# 1-Schematic_8052Explorer_JOLLY.net
KiCad netlist of a schematic drawn in EasyEDA
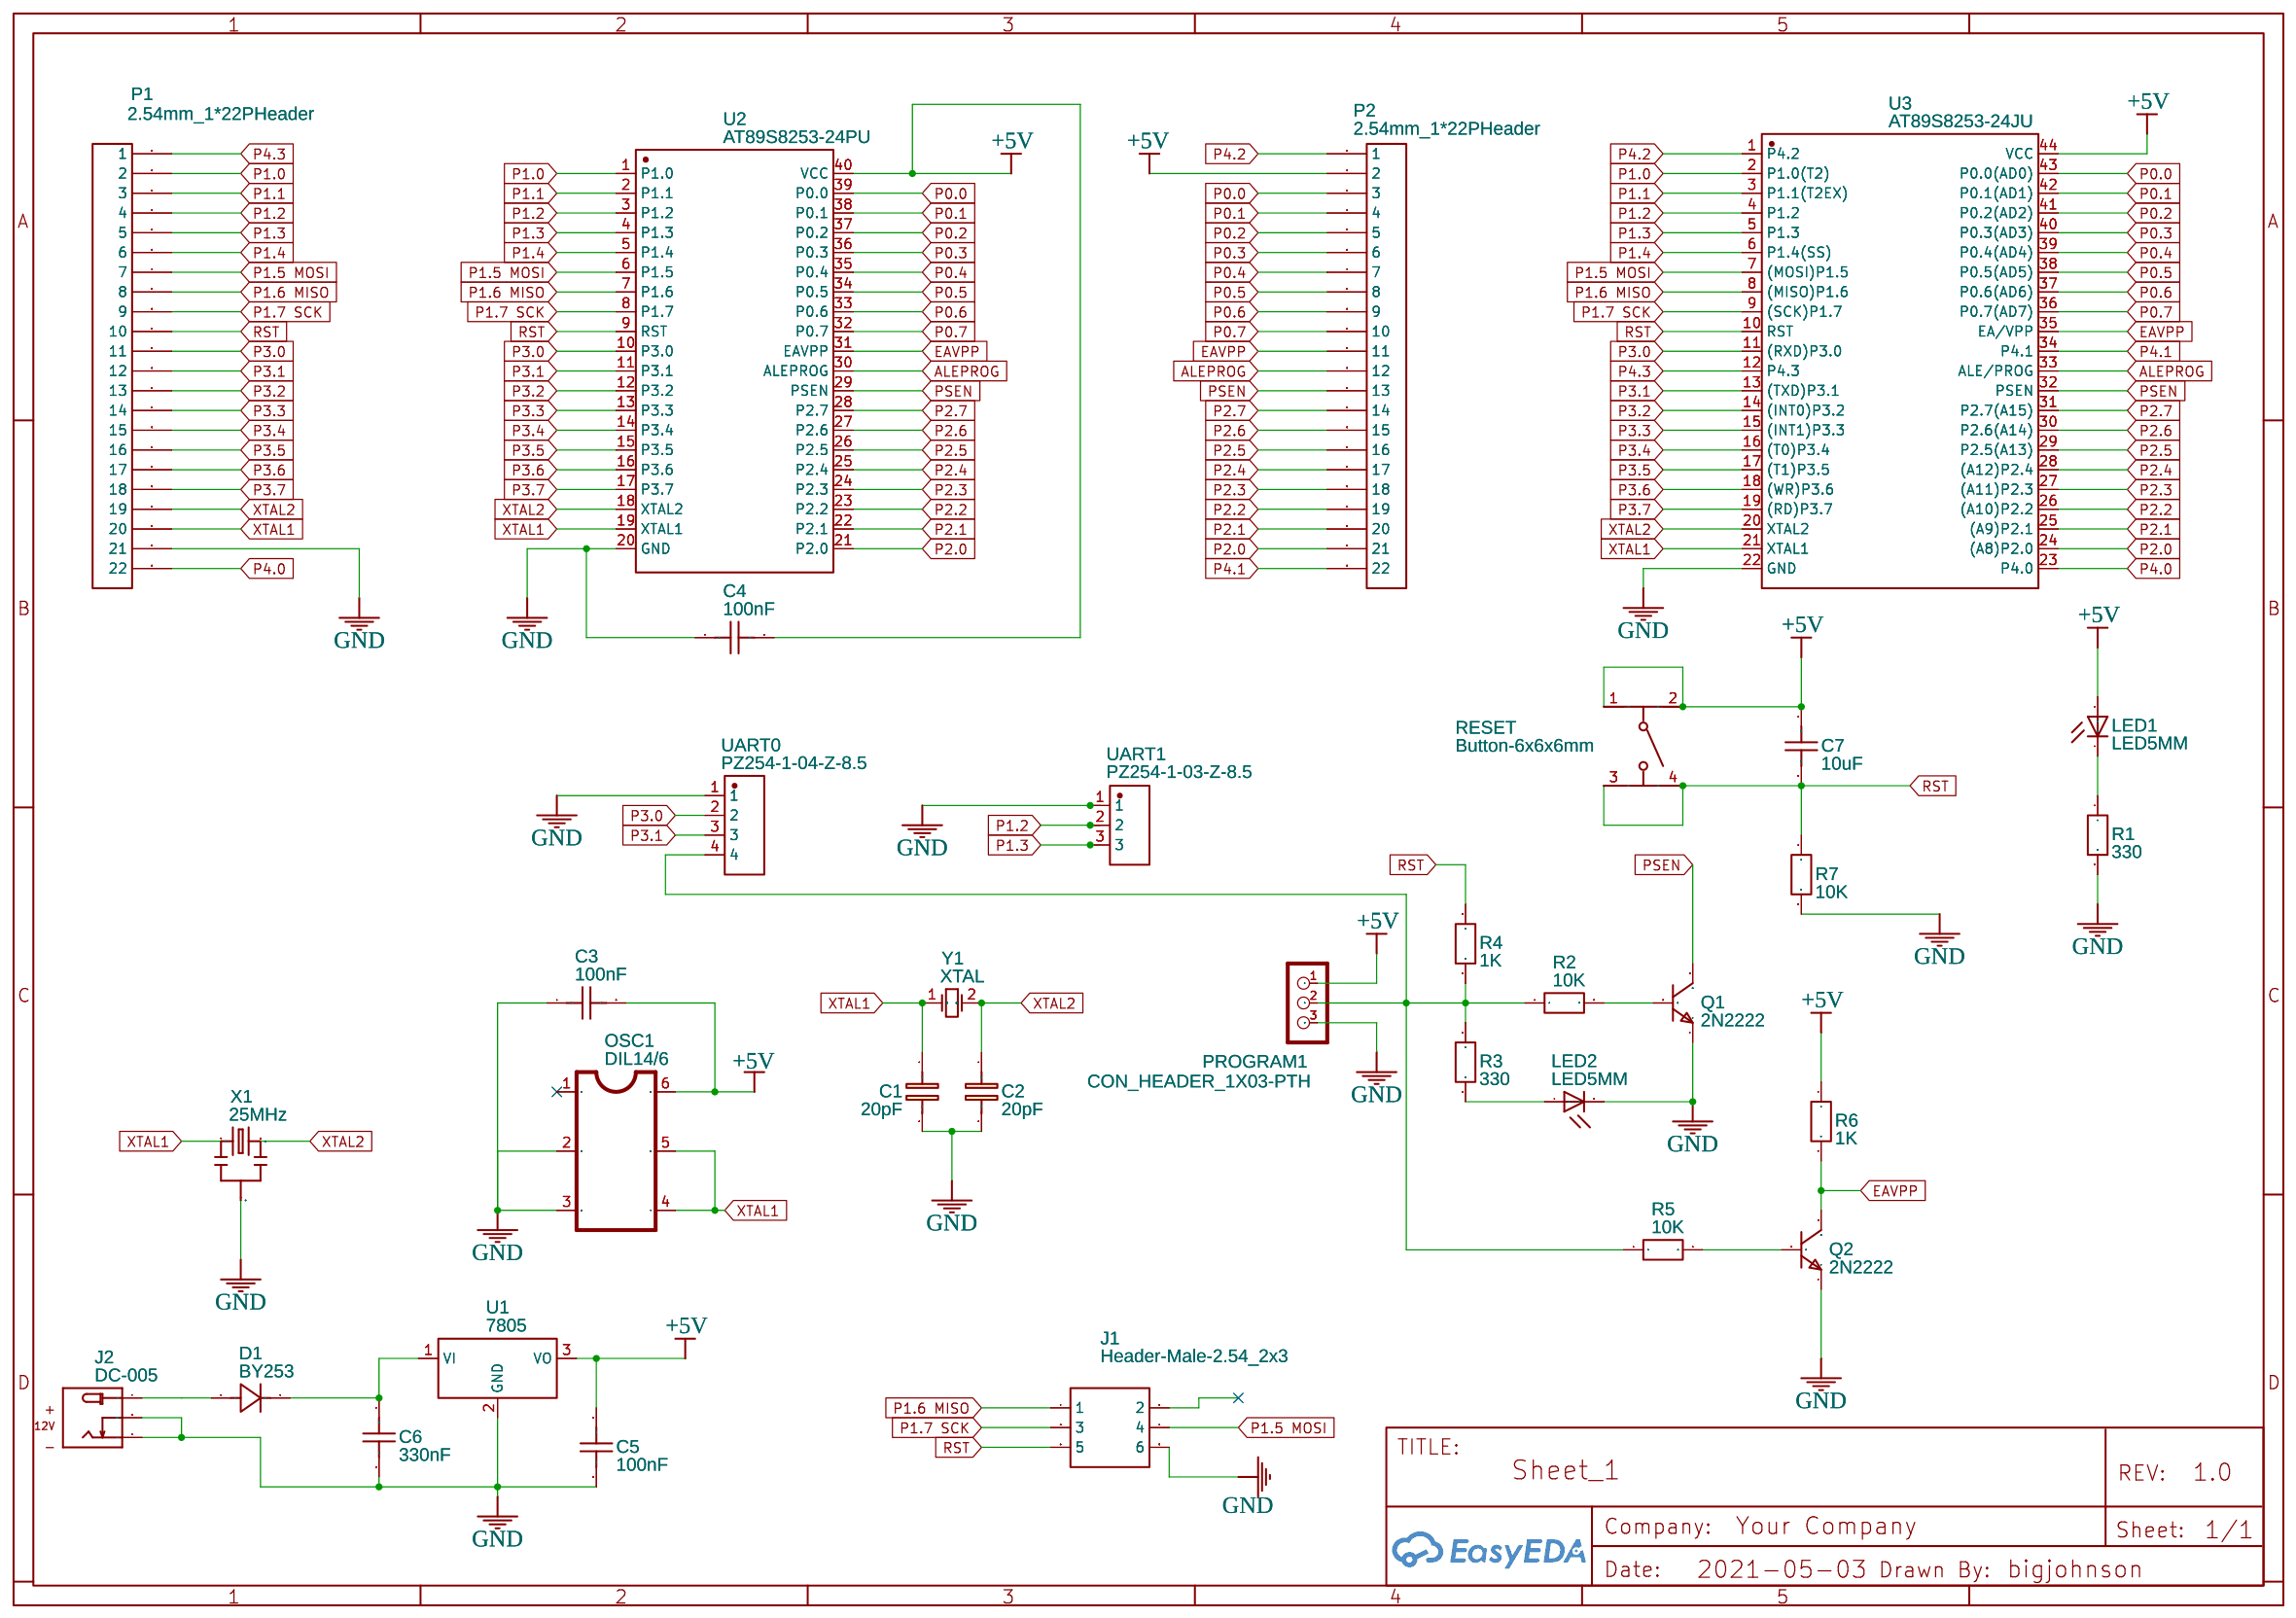
[diagram p0: schematic sheet]

(export (version "E")
  (design (tool "Eeschema 10.0.6"))
  (components
    (comp (ref "C1")
      (value "20pF")
      (fields (field (name "BOM_Supplier Part") "9000274010"))
      (libsource (lib "") (part "20pF copy"))
    )
    (comp (ref "C2")
      (value "20pF")
      (fields (field (name "BOM_Supplier Part") "9000274010"))
      (libsource (lib "") (part "20pF copy"))
    )
    (comp (ref "C3")
      (value "100nF")
      (fields
        (field (name "BOM_Manufacturer Part") "CT4-0805B103 K500")
        (field (name "BOM_Supplier Part") "C8033")
      )
      (libsource (lib "") (part "CT4-0805B103 K500"))
    )
    (comp (ref "C4")
      (value "100nF")
      (fields
        (field (name "BOM_Manufacturer Part") "CT4-0805B103 K500")
        (field (name "BOM_Supplier Part") "C8033")
      )
      (libsource (lib "") (part "CT4-0805B103 K500"))
    )
    (comp (ref "C5")
      (value "100nF")
      (fields
        (field (name "BOM_Manufacturer Part") "CT4-0805B103 K500")
        (field (name "BOM_Supplier Part") "C8033")
      )
      (libsource (lib "") (part "CT4-0805B103 K500_1"))
    )
    (comp (ref "C6")
      (value "330nF")
      (fields
        (field (name "BOM_Manufacturer Part") "CT4-0805B103 K500")
        (field (name "BOM_Supplier Part") "C8033")
      )
      (libsource (lib "") (part "CT4-0805B103 K500_1"))
    )
    (comp (ref "C7")
      (value "10uF")
      (fields
        (field (name "BOM_Manufacturer Part") "CT4-0805B103 K500")
        (field (name "BOM_Supplier Part") "C8033")
      )
      (libsource (lib "") (part "CT4-0805B103 K500_1"))
    )
    (comp (ref "D1")
      (value "BY253")
      (fields (field (name "BOM_Manufacturer Part") "MUR460") (field (name "BOM_Supplier Part") "C2990844"))
      (libsource (lib "") (part "MUR460_C2990844"))
    )
    (comp (ref "J1")
      (value "Header-Male-2.54_2x3")
      (fields (field (name "BOM_Supplier Part") "C65114"))
      (libsource (lib "") (part "Header-Male-2.54_2x3"))
    )
    (comp (ref "J2") (value "DC-005") (libsource (lib "") (part "DC-005")))
    (comp (ref "LED1") (value "LED5MM") (libsource (lib "") (part "LED5MM_1")))
    (comp (ref "LED2") (value "LED5MM") (libsource (lib "") (part "LED5MM")))
    (comp (ref "OSC1") (value "DIL14/6") (libsource (lib "") (part "DIL14/3")))
    (comp (ref "P1")
      (value "2.54mm_1*22PHeader")
      (fields
        (field (name "BOM_Manufacturer Part") "2.54mm 1*22PHeader")
        (field (name "BOM_Supplier Part") "C50981")
      )
      (libsource (lib "") (part "2.54mm_1*22PHeader_1"))
    )
    (comp (ref "P2")
      (value "2.54mm_1*22PHeader")
      (fields
        (field (name "BOM_Manufacturer Part") "2.54mm 1*22PHeader")
        (field (name "BOM_Supplier Part") "C50981")
      )
      (libsource (lib "") (part "2.54mm_1*22PHeader"))
    )
    (comp (ref "PROGRAM1") (value "CON_HEADER_1X03-PTH") (libsource (lib "") (part "CON_HEADER_1X03-PTH")))
    (comp (ref "Q1")
      (value "2N2222")
      (fields (field (name "BOM_Supplier Part") "C118536"))
      (libsource (lib "") (part "2N2222"))
    )
    (comp (ref "Q2")
      (value "2N2222")
      (fields (field (name "BOM_Supplier Part") "C118536"))
      (libsource (lib "") (part "2N2222"))
    )
    (comp (ref "R1") (value "330") (libsource (lib "") (part "Res_AXIAL-0.4(1/4W)_EU")))
    (comp (ref "R2") (value "10K") (libsource (lib "") (part "Res_AXIAL-0.4(1/4W)_EU_1")))
    (comp (ref "R3") (value "330") (libsource (lib "") (part "Res_AXIAL-0.4(1/4W)_EU")))
    (comp (ref "R4") (value "1K") (libsource (lib "") (part "Res_AXIAL-0.4(1/4W)_EU")))
    (comp (ref "R5") (value "10K") (libsource (lib "") (part "Res_AXIAL-0.4(1/4W)_EU_1")))
    (comp (ref "R6") (value "1K") (libsource (lib "") (part "Res_AXIAL-0.4(1/4W)_EU")))
    (comp (ref "R7") (value "10K") (libsource (lib "") (part "Res_AXIAL-0.4(1/4W)_EU")))
    (comp (ref "RESET")
      (value "Button-6x6x6mm")
      (fields
        (field (name "BOM_Manufacturer Part") "Switch,6*6*6Plastic head,260G, 0.25mm,Straight line")
        (field (name "BOM_Supplier Part") "C71836")
      )
      (libsource (lib "") (part "Button-6x6x6mm"))
    )
    (comp (ref "U1")
      (value "7805")
      (fields (field (name "BOM_Supplier Part") "C305416"))
      (libsource (lib "") (part "7805"))
    )
    (comp (ref "U2") (value "AT89S8253-24PU") (libsource (lib "") (part "AT89S8253-24PU")))
    (comp (ref "U3")
      (value "AT89S8253-24JU")
      (fields (field (name "BOM_Supplier Part") "C614054"))
      (libsource (lib "") (part "AT89S8253-24JU"))
    )
    (comp (ref "UART0")
      (value "PZ254-1-04-Z-8.5")
      (fields (field (name "BOM_Supplier Part") "C2894927"))
      (libsource (lib "") (part "PZ254-1-04-Z-8.5"))
    )
    (comp (ref "UART1")
      (value "PZ254-1-03-Z-8.5")
      (fields (field (name "BOM_Supplier Part") "C2894926"))
      (libsource (lib "") (part "PZ254-1-03-Z-8.5"))
    )
    (comp (ref "X1")
      (value "25MHz")
      (fields
        (field (name "BOM_Manufacturer Part") "Resonator 433.92MHZ")
        (field (name "BOM_Supplier Part") "C71016")
      )
      (libsource (lib "") (part "Ceramic Resonator 16 MHz"))
    )
    (comp (ref "Y1") (value "XTAL") (libsource (lib "") (part "XTAL")))
  )
  (nets
    (net (code "1") (name "+5V") (class "Default")
      (node (ref "C3") (pin "2") (pinfunction "2_2") (pintype "unspecified"))
      (node (ref "C4") (pin "2") (pinfunction "2_2") (pintype "unspecified"))
      (node (ref "C5") (pin "1") (pinfunction "1_1") (pintype "unspecified"))
      (node (ref "C7") (pin "1") (pinfunction "1_1") (pintype "unspecified"))
      (node (ref "LED1") (pin "A") (pinfunction "A_A") (pintype "unspecified"))
      (node (ref "OSC1") (pin "6") (pinfunction "6_6") (pintype "unspecified"))
      (node (ref "P2") (pin "2") (pinfunction "2_2") (pintype "input"))
      (node (ref "PROGRAM1") (pin "1") (pinfunction "1_1") (pintype "unspecified"))
      (node (ref "R6") (pin "1") (pinfunction "1_1") (pintype "unspecified"))
      (node (ref "RESET") (pin "1") (pinfunction "1_1") (pintype "unspecified"))
      (node (ref "RESET") (pin "2") (pinfunction "2_2") (pintype "unspecified"))
      (node (ref "U1") (pin "3") (pinfunction "VO_3") (pintype "unspecified"))
      (node (ref "U2") (pin "40") (pinfunction "VCC_40") (pintype "unspecified"))
      (node (ref "U3") (pin "44") (pinfunction "VCC_44") (pintype "unspecified"))
    )
    (net (code "2") (name "ALEPROG") (class "Default")
      (node (ref "P2") (pin "12") (pinfunction "12_12") (pintype "input"))
      (node (ref "U2") (pin "30") (pinfunction "ALEPROG_30") (pintype "unspecified"))
      (node (ref "U3") (pin "33") (pinfunction "ALE/PROG_33") (pintype "unspecified"))
    )
    (net (code "3") (name "EAVPP") (class "Default")
      (node (ref "P2") (pin "11") (pinfunction "11_11") (pintype "input"))
      (node (ref "Q2") (pin "3") (pinfunction "C_3") (pintype "unspecified"))
      (node (ref "R6") (pin "2") (pinfunction "2_2") (pintype "unspecified"))
      (node (ref "U2") (pin "31") (pinfunction "EAVPP_31") (pintype "unspecified"))
      (node (ref "U3") (pin "35") (pinfunction "EA/VPP_35") (pintype "unspecified"))
    )
    (net (code "4") (name "GND") (class "Default")
      (node (ref "C1") (pin "2") (pinfunction "1_2") (pintype "unspecified"))
      (node (ref "C2") (pin "2") (pinfunction "1_2") (pintype "unspecified"))
      (node (ref "C3") (pin "1") (pinfunction "1_1") (pintype "unspecified"))
      (node (ref "C4") (pin "1") (pinfunction "1_1") (pintype "unspecified"))
      (node (ref "C5") (pin "2") (pinfunction "2_2") (pintype "unspecified"))
      (node (ref "C6") (pin "2") (pinfunction "2_2") (pintype "unspecified"))
      (node (ref "J1") (pin "6") (pinfunction "6_6") (pintype "input"))
      (node (ref "J2") (pin "-1") (pinfunction "-_-1") (pintype "unspecified"))
      (node (ref "J2") (pin "-2") (pinfunction "CDN_-2") (pintype "unspecified"))
      (node (ref "LED2") (pin "K") (pinfunction "C_K") (pintype "unspecified"))
      (node (ref "OSC1") (pin "2") (pinfunction "2_2") (pintype "unspecified"))
      (node (ref "OSC1") (pin "3") (pinfunction "3_3") (pintype "unspecified"))
      (node (ref "P1") (pin "21") (pinfunction "21_21") (pintype "unspecified"))
      (node (ref "PROGRAM1") (pin "3") (pinfunction "3_3") (pintype "unspecified"))
      (node (ref "Q1") (pin "1") (pinfunction "E_1") (pintype "unspecified"))
      (node (ref "Q2") (pin "1") (pinfunction "E_1") (pintype "unspecified"))
      (node (ref "R1") (pin "2") (pinfunction "2_2") (pintype "unspecified"))
      (node (ref "R7") (pin "2") (pinfunction "2_2") (pintype "unspecified"))
      (node (ref "U1") (pin "2") (pinfunction "GND_2") (pintype "unspecified"))
      (node (ref "U2") (pin "20") (pinfunction "GND_20") (pintype "unspecified"))
      (node (ref "U3") (pin "22") (pinfunction "GND_22") (pintype "unspecified"))
      (node (ref "UART0") (pin "1") (pinfunction "1_1") (pintype "unspecified"))
      (node (ref "UART1") (pin "1") (pinfunction "1_1") (pintype "unspecified"))
      (node (ref "X1") (pin "2") (pinfunction "2_2") (pintype "unspecified"))
    )
    (net (code "5") (name "Net-(D1-A)") (class "Default")
      (node (ref "D1") (pin "2") (pinfunction "A_2") (pintype "unspecified"))
      (node (ref "J2") (pin "+") (pinfunction "+_+") (pintype "unspecified"))
    )
    (net (code "6") (name "Net-(D1-K)") (class "Default")
      (node (ref "C6") (pin "1") (pinfunction "1_1") (pintype "unspecified"))
      (node (ref "D1") (pin "1") (pinfunction "K_1") (pintype "unspecified"))
      (node (ref "U1") (pin "1") (pinfunction "VI_1") (pintype "unspecified"))
    )
    (net (code "7") (name "Net-(LED1-C)") (class "Default")
      (node (ref "LED1") (pin "K") (pinfunction "C_K") (pintype "unspecified"))
      (node (ref "R1") (pin "1") (pinfunction "1_1") (pintype "unspecified"))
    )
    (net (code "8") (name "Net-(LED2-PadA)") (class "Default")
      (node (ref "LED2") (pin "A") (pinfunction "A_A") (pintype "unspecified"))
      (node (ref "R3") (pin "2") (pinfunction "2_2") (pintype "unspecified"))
    )
    (net (code "9") (name "Net-(PROGRAM1-Pad2)") (class "Default")
      (node (ref "PROGRAM1") (pin "2") (pinfunction "2_2") (pintype "unspecified"))
      (node (ref "R2") (pin "1") (pinfunction "1_1") (pintype "unspecified"))
      (node (ref "R3") (pin "1") (pinfunction "1_1") (pintype "unspecified"))
      (node (ref "R4") (pin "2") (pinfunction "2_2") (pintype "unspecified"))
      (node (ref "R5") (pin "1") (pinfunction "1_1") (pintype "unspecified"))
      (node (ref "UART0") (pin "4") (pinfunction "4_4") (pintype "unspecified"))
    )
    (net (code "10") (name "Net-(Q1-B)") (class "Default")
      (node (ref "Q1") (pin "2") (pinfunction "B_2") (pintype "unspecified"))
      (node (ref "R2") (pin "2") (pinfunction "2_2") (pintype "unspecified"))
    )
    (net (code "11") (name "Net-(Q2-B)") (class "Default")
      (node (ref "Q2") (pin "2") (pinfunction "B_2") (pintype "unspecified"))
      (node (ref "R5") (pin "2") (pinfunction "2_2") (pintype "unspecified"))
    )
    (net (code "12") (name "P0.0") (class "Default")
      (node (ref "P2") (pin "3") (pinfunction "3_3") (pintype "input"))
      (node (ref "U2") (pin "39") (pinfunction "P0.0_39") (pintype "unspecified"))
      (node (ref "U3") (pin "43") (pinfunction "P0.0(AD0)_43") (pintype "unspecified"))
    )
    (net (code "13") (name "P0.1") (class "Default")
      (node (ref "P2") (pin "4") (pinfunction "4_4") (pintype "input"))
      (node (ref "U2") (pin "38") (pinfunction "P0.1_38") (pintype "unspecified"))
      (node (ref "U3") (pin "42") (pinfunction "P0.1(AD1)_42") (pintype "unspecified"))
    )
    (net (code "14") (name "P0.2") (class "Default")
      (node (ref "P2") (pin "5") (pinfunction "5_5") (pintype "input"))
      (node (ref "U2") (pin "37") (pinfunction "P0.2_37") (pintype "unspecified"))
      (node (ref "U3") (pin "41") (pinfunction "P0.2(AD2)_41") (pintype "unspecified"))
    )
    (net (code "15") (name "P0.3") (class "Default")
      (node (ref "P2") (pin "6") (pinfunction "6_6") (pintype "input"))
      (node (ref "U2") (pin "36") (pinfunction "P0.3_36") (pintype "unspecified"))
      (node (ref "U3") (pin "40") (pinfunction "P0.3(AD3)_40") (pintype "unspecified"))
    )
    (net (code "16") (name "P0.4") (class "Default")
      (node (ref "P2") (pin "7") (pinfunction "7_7") (pintype "input"))
      (node (ref "U2") (pin "35") (pinfunction "P0.4_35") (pintype "unspecified"))
      (node (ref "U3") (pin "39") (pinfunction "P0.4(AD4)_39") (pintype "unspecified"))
    )
    (net (code "17") (name "P0.5") (class "Default")
      (node (ref "P2") (pin "8") (pinfunction "8_8") (pintype "input"))
      (node (ref "U2") (pin "34") (pinfunction "P0.5_34") (pintype "unspecified"))
      (node (ref "U3") (pin "38") (pinfunction "P0.5(AD5)_38") (pintype "unspecified"))
    )
    (net (code "18") (name "P0.6") (class "Default")
      (node (ref "P2") (pin "9") (pinfunction "9_9") (pintype "input"))
      (node (ref "U2") (pin "33") (pinfunction "P0.6_33") (pintype "unspecified"))
      (node (ref "U3") (pin "37") (pinfunction "P0.6(AD6)_37") (pintype "unspecified"))
    )
    (net (code "19") (name "P0.7") (class "Default")
      (node (ref "P2") (pin "10") (pinfunction "10_10") (pintype "input"))
      (node (ref "U2") (pin "32") (pinfunction "P0.7_32") (pintype "unspecified"))
      (node (ref "U3") (pin "36") (pinfunction "P0.7(AD7)_36") (pintype "unspecified"))
    )
    (net (code "20") (name "P1.0") (class "Default")
      (node (ref "P1") (pin "2") (pinfunction "2_2") (pintype "input"))
      (node (ref "U2") (pin "1") (pinfunction "P1.0_1") (pintype "unspecified"))
      (node (ref "U3") (pin "2") (pinfunction "P1.0(T2)_2") (pintype "unspecified"))
    )
    (net (code "21") (name "P1.1") (class "Default")
      (node (ref "P1") (pin "3") (pinfunction "3_3") (pintype "input"))
      (node (ref "U2") (pin "2") (pinfunction "P1.1_2") (pintype "unspecified"))
      (node (ref "U3") (pin "3") (pinfunction "P1.1(T2EX)_3") (pintype "unspecified"))
    )
    (net (code "22") (name "P1.2") (class "Default")
      (node (ref "P1") (pin "4") (pinfunction "4_4") (pintype "input"))
      (node (ref "U2") (pin "3") (pinfunction "P1.2_3") (pintype "unspecified"))
      (node (ref "U3") (pin "4") (pinfunction "P1.2_4") (pintype "unspecified"))
      (node (ref "UART1") (pin "2") (pinfunction "2_2") (pintype "unspecified"))
    )
    (net (code "23") (name "P1.3") (class "Default")
      (node (ref "P1") (pin "5") (pinfunction "5_5") (pintype "input"))
      (node (ref "U2") (pin "4") (pinfunction "P1.3_4") (pintype "unspecified"))
      (node (ref "U3") (pin "5") (pinfunction "P1.3_5") (pintype "unspecified"))
      (node (ref "UART1") (pin "3") (pinfunction "3_3") (pintype "unspecified"))
    )
    (net (code "24") (name "P1.4") (class "Default")
      (node (ref "P1") (pin "6") (pinfunction "6_6") (pintype "input"))
      (node (ref "U2") (pin "5") (pinfunction "P1.4_5") (pintype "unspecified"))
      (node (ref "U3") (pin "6") (pinfunction "P1.4(SS)_6") (pintype "unspecified"))
    )
    (net (code "25") (name "P1.5 MOSI") (class "Default")
      (node (ref "J1") (pin "4") (pinfunction "4_4") (pintype "input"))
      (node (ref "P1") (pin "7") (pinfunction "7_7") (pintype "input"))
      (node (ref "U2") (pin "6") (pinfunction "P1.5_6") (pintype "unspecified"))
      (node (ref "U3") (pin "7") (pinfunction "(MOSI)P1.5_7") (pintype "unspecified"))
    )
    (net (code "26") (name "P1.6 MISO") (class "Default")
      (node (ref "J1") (pin "1") (pinfunction "1_1") (pintype "input"))
      (node (ref "P1") (pin "8") (pinfunction "8_8") (pintype "input"))
      (node (ref "U2") (pin "7") (pinfunction "P1.6_7") (pintype "unspecified"))
      (node (ref "U3") (pin "8") (pinfunction "(MISO)P1.6_8") (pintype "unspecified"))
    )
    (net (code "27") (name "P1.7 SCK") (class "Default")
      (node (ref "J1") (pin "3") (pinfunction "3_3") (pintype "input"))
      (node (ref "P1") (pin "9") (pinfunction "9_9") (pintype "input"))
      (node (ref "U2") (pin "8") (pinfunction "P1.7_8") (pintype "unspecified"))
      (node (ref "U3") (pin "9") (pinfunction "(SCK)P1.7_9") (pintype "unspecified"))
    )
    (net (code "28") (name "P2.0") (class "Default")
      (node (ref "P2") (pin "21") (pinfunction "21_21") (pintype "unspecified"))
      (node (ref "U2") (pin "21") (pinfunction "P2.0_21") (pintype "unspecified"))
      (node (ref "U3") (pin "24") (pinfunction "(A8)P2.0_24") (pintype "unspecified"))
    )
    (net (code "29") (name "P2.1") (class "Default")
      (node (ref "P2") (pin "20") (pinfunction "20_20") (pintype "input"))
      (node (ref "U2") (pin "22") (pinfunction "P2.1_22") (pintype "unspecified"))
      (node (ref "U3") (pin "25") (pinfunction "(A9)P2.1_25") (pintype "unspecified"))
    )
    (net (code "30") (name "P2.2") (class "Default")
      (node (ref "P2") (pin "19") (pinfunction "19_19") (pintype "input"))
      (node (ref "U2") (pin "23") (pinfunction "P2.2_23") (pintype "unspecified"))
      (node (ref "U3") (pin "26") (pinfunction "(A10)P2.2_26") (pintype "unspecified"))
    )
    (net (code "31") (name "P2.3") (class "Default")
      (node (ref "P2") (pin "18") (pinfunction "18_18") (pintype "input"))
      (node (ref "U2") (pin "24") (pinfunction "P2.3_24") (pintype "unspecified"))
      (node (ref "U3") (pin "27") (pinfunction "(A11)P2.3_27") (pintype "unspecified"))
    )
    (net (code "32") (name "P2.4") (class "Default")
      (node (ref "P2") (pin "17") (pinfunction "17_17") (pintype "input"))
      (node (ref "U2") (pin "25") (pinfunction "P2.4_25") (pintype "unspecified"))
      (node (ref "U3") (pin "28") (pinfunction "(A12)P2.4_28") (pintype "unspecified"))
    )
    (net (code "33") (name "P2.5") (class "Default")
      (node (ref "P2") (pin "16") (pinfunction "16_16") (pintype "input"))
      (node (ref "U2") (pin "26") (pinfunction "P2.5_26") (pintype "unspecified"))
      (node (ref "U3") (pin "29") (pinfunction "P2.5(A13)_29") (pintype "unspecified"))
    )
    (net (code "34") (name "P2.6") (class "Default")
      (node (ref "P2") (pin "15") (pinfunction "15_15") (pintype "input"))
      (node (ref "U2") (pin "27") (pinfunction "P2.6_27") (pintype "unspecified"))
      (node (ref "U3") (pin "30") (pinfunction "P2.6(A14)_30") (pintype "unspecified"))
    )
    (net (code "35") (name "P2.7") (class "Default")
      (node (ref "P2") (pin "14") (pinfunction "14_14") (pintype "input"))
      (node (ref "U2") (pin "28") (pinfunction "P2.7_28") (pintype "unspecified"))
      (node (ref "U3") (pin "31") (pinfunction "P2.7(A15)_31") (pintype "unspecified"))
    )
    (net (code "36") (name "P3.0") (class "Default")
      (node (ref "P1") (pin "11") (pinfunction "11_11") (pintype "input"))
      (node (ref "U2") (pin "10") (pinfunction "P3.0_10") (pintype "unspecified"))
      (node (ref "U3") (pin "11") (pinfunction "(RXD)P3.0_11") (pintype "unspecified"))
      (node (ref "UART0") (pin "2") (pinfunction "2_2") (pintype "unspecified"))
    )
    (net (code "37") (name "P3.1") (class "Default")
      (node (ref "P1") (pin "12") (pinfunction "12_12") (pintype "input"))
      (node (ref "U2") (pin "11") (pinfunction "P3.1_11") (pintype "unspecified"))
      (node (ref "U3") (pin "13") (pinfunction "(TXD)P3.1_13") (pintype "unspecified"))
      (node (ref "UART0") (pin "3") (pinfunction "3_3") (pintype "unspecified"))
    )
    (net (code "38") (name "P3.2") (class "Default")
      (node (ref "P1") (pin "13") (pinfunction "13_13") (pintype "input"))
      (node (ref "U2") (pin "12") (pinfunction "P3.2_12") (pintype "unspecified"))
      (node (ref "U3") (pin "14") (pinfunction "(INT0)P3.2_14") (pintype "unspecified"))
    )
    (net (code "39") (name "P3.3") (class "Default")
      (node (ref "P1") (pin "14") (pinfunction "14_14") (pintype "input"))
      (node (ref "U2") (pin "13") (pinfunction "P3.3_13") (pintype "unspecified"))
      (node (ref "U3") (pin "15") (pinfunction "(INT1)P3.3_15") (pintype "unspecified"))
    )
    (net (code "40") (name "P3.4") (class "Default")
      (node (ref "P1") (pin "15") (pinfunction "15_15") (pintype "input"))
      (node (ref "U2") (pin "14") (pinfunction "P3.4_14") (pintype "unspecified"))
      (node (ref "U3") (pin "16") (pinfunction "(T0)P3.4_16") (pintype "unspecified"))
    )
    (net (code "41") (name "P3.5") (class "Default")
      (node (ref "P1") (pin "16") (pinfunction "16_16") (pintype "input"))
      (node (ref "U2") (pin "15") (pinfunction "P3.5_15") (pintype "unspecified"))
      (node (ref "U3") (pin "17") (pinfunction "(T1)P3.5_17") (pintype "unspecified"))
    )
    (net (code "42") (name "P3.6") (class "Default")
      (node (ref "P1") (pin "17") (pinfunction "17_17") (pintype "input"))
      (node (ref "U2") (pin "16") (pinfunction "P3.6_16") (pintype "unspecified"))
      (node (ref "U3") (pin "18") (pinfunction "(WR)P3.6_18") (pintype "unspecified"))
    )
    (net (code "43") (name "P3.7") (class "Default")
      (node (ref "P1") (pin "18") (pinfunction "18_18") (pintype "input"))
      (node (ref "U2") (pin "17") (pinfunction "P3.7_17") (pintype "unspecified"))
      (node (ref "U3") (pin "19") (pinfunction "(RD)P3.7_19") (pintype "unspecified"))
    )
    (net (code "44") (name "P4.0") (class "Default")
      (node (ref "P1") (pin "22") (pinfunction "22_22") (pintype "unspecified"))
      (node (ref "U3") (pin "23") (pinfunction "P4.0_23") (pintype "unspecified"))
    )
    (net (code "45") (name "P4.1") (class "Default")
      (node (ref "P2") (pin "22") (pinfunction "22_22") (pintype "unspecified"))
      (node (ref "U3") (pin "34") (pinfunction "P4.1_34") (pintype "unspecified"))
    )
    (net (code "46") (name "P4.2") (class "Default")
      (node (ref "P2") (pin "1") (pinfunction "1_1") (pintype "input"))
      (node (ref "U3") (pin "1") (pinfunction "P4.2_1") (pintype "unspecified"))
    )
    (net (code "47") (name "P4.3") (class "Default")
      (node (ref "P1") (pin "1") (pinfunction "1_1") (pintype "input"))
      (node (ref "U3") (pin "12") (pinfunction "P4.3_12") (pintype "unspecified"))
    )
    (net (code "48") (name "PSEN") (class "Default")
      (node (ref "P2") (pin "13") (pinfunction "13_13") (pintype "input"))
      (node (ref "Q1") (pin "3") (pinfunction "C_3") (pintype "unspecified"))
      (node (ref "U2") (pin "29") (pinfunction "PSEN_29") (pintype "unspecified"))
      (node (ref "U3") (pin "32") (pinfunction "PSEN_32") (pintype "unspecified"))
    )
    (net (code "49") (name "RST") (class "Default")
      (node (ref "C7") (pin "2") (pinfunction "2_2") (pintype "unspecified"))
      (node (ref "J1") (pin "5") (pinfunction "5_5") (pintype "input"))
      (node (ref "P1") (pin "10") (pinfunction "10_10") (pintype "input"))
      (node (ref "R4") (pin "1") (pinfunction "1_1") (pintype "unspecified"))
      (node (ref "R7") (pin "1") (pinfunction "1_1") (pintype "unspecified"))
      (node (ref "RESET") (pin "3") (pinfunction "3_3") (pintype "unspecified"))
      (node (ref "RESET") (pin "4") (pinfunction "4_4") (pintype "unspecified"))
      (node (ref "U2") (pin "9") (pinfunction "RST_9") (pintype "unspecified"))
      (node (ref "U3") (pin "10") (pinfunction "RST_10") (pintype "unspecified"))
    )
    (net (code "50") (name "XTAL1") (class "Default")
      (node (ref "C1") (pin "1") (pinfunction "1_1") (pintype "unspecified"))
      (node (ref "OSC1") (pin "4") (pinfunction "4_4") (pintype "unspecified"))
      (node (ref "OSC1") (pin "5") (pinfunction "5_5") (pintype "unspecified"))
      (node (ref "P1") (pin "20") (pinfunction "20_20") (pintype "input"))
      (node (ref "U2") (pin "19") (pinfunction "XTAL1_19") (pintype "unspecified"))
      (node (ref "U3") (pin "21") (pinfunction "XTAL1_21") (pintype "unspecified"))
      (node (ref "X1") (pin "1") (pinfunction "1_1") (pintype "unspecified"))
      (node (ref "Y1") (pin "1") (pinfunction "OSC1_1") (pintype "unspecified"))
    )
    (net (code "51") (name "XTAL2") (class "Default")
      (node (ref "C2") (pin "1") (pinfunction "1_1") (pintype "unspecified"))
      (node (ref "P1") (pin "19") (pinfunction "19_19") (pintype "input"))
      (node (ref "U2") (pin "18") (pinfunction "XTAL2_18") (pintype "unspecified"))
      (node (ref "U3") (pin "20") (pinfunction "XTAL2_20") (pintype "unspecified"))
      (node (ref "X1") (pin "3") (pinfunction "3_3") (pintype "unspecified"))
      (node (ref "Y1") (pin "2") (pinfunction "OSC2_2") (pintype "unspecified"))
    )
    (net (code "52") (name "unconnected-(J1-Pad2)") (class "Default")
      (node (ref "J1") (pin "2") (pinfunction "2_2") (pintype "input+no_connect"))
    )
    (net (code "53") (name "unconnected-(OSC1-Pad1)") (class "Default")
      (node (ref "OSC1") (pin "1") (pinfunction "1_1") (pintype "unspecified+no_connect"))
    )
  )
)
